# IoT_modules_atmega328_kinemata_v2.net
KiCad netlist of a schematic drawn in EAGLE
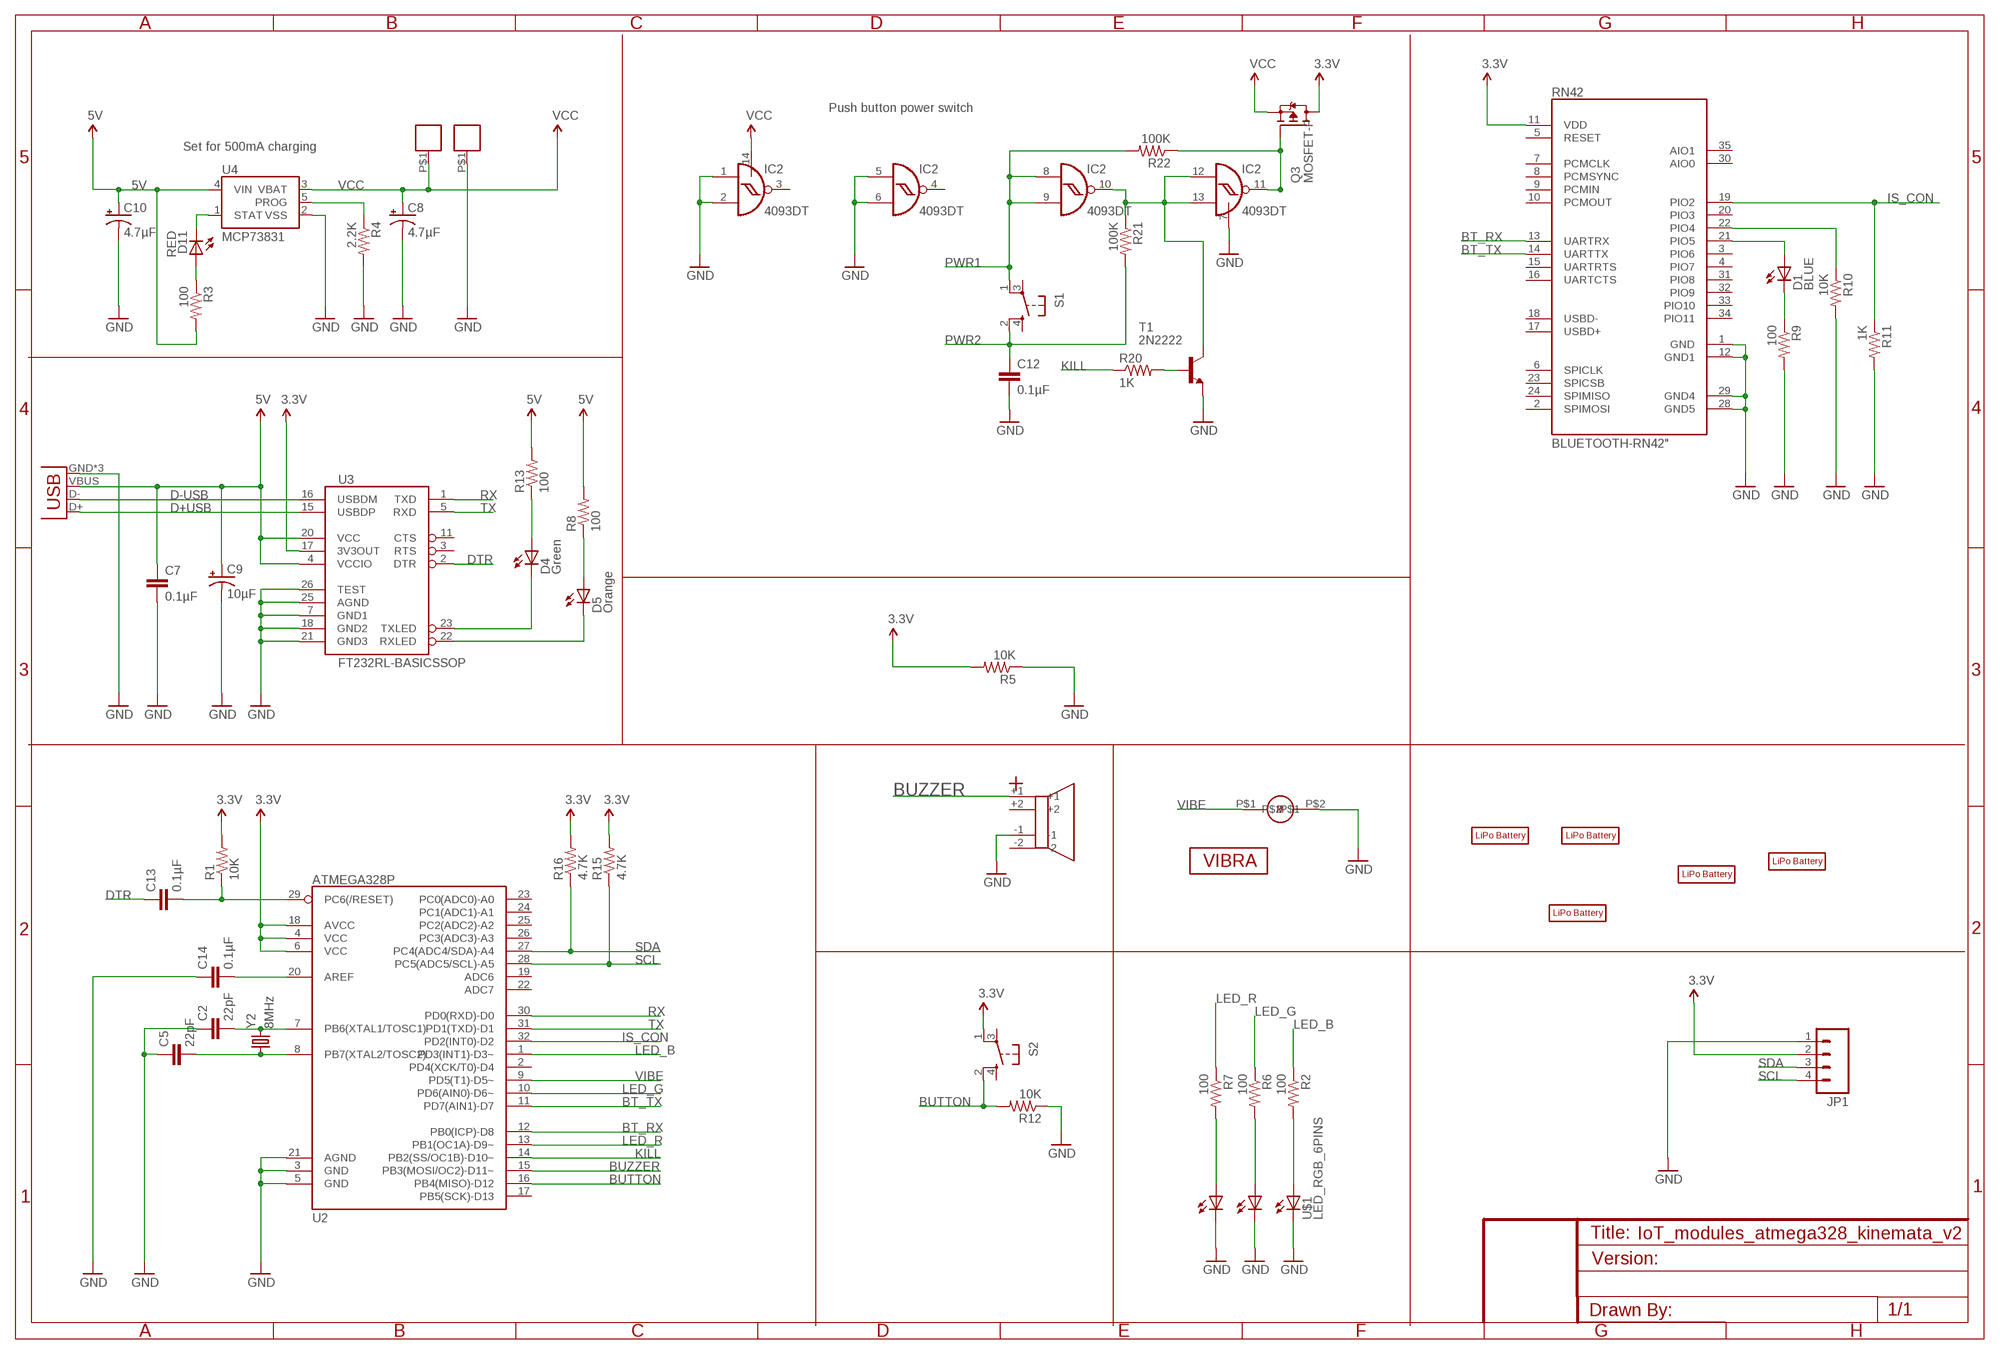
[diagram p0: schematic, sheet 1]

(export (version "E")
  (design (tool "Eeschema 10.0.6"))
  (components
    (comp (ref "BAT+2")
      (value "LIPO_PAD")
      (footprint "eagle-import:LIPO_PAD")
      (libsource (lib "eagle-import") (part "LIPO_PAD"))
    )
    (comp (ref "BAT-1")
      (value "LIPO_PAD")
      (footprint "eagle-import:LIPO_PAD")
      (libsource (lib "eagle-import") (part "LIPO_PAD"))
    )
    (comp (ref "C2")
      (value "22pF")
      (footprint "eagle-import:1206")
      (libsource (lib "eagle-import") (part "CAP1206"))
    )
    (comp (ref "C5")
      (value "22pF")
      (footprint "eagle-import:1206")
      (libsource (lib "eagle-import") (part "CAP1206"))
    )
    (comp (ref "C7")
      (value "0.1µF")
      (footprint "eagle-import:1206")
      (libsource (lib "eagle-import") (part "CAP1206"))
    )
    (comp (ref "C8")
      (value "4.7µF")
      (footprint "eagle-import:EIA3216")
      (libsource (lib "eagle-import") (part "CAP_POL1206"))
    )
    (comp (ref "C9")
      (value "10µF")
      (footprint "eagle-import:EIA3216")
      (libsource (lib "eagle-import") (part "CAP_POL1206"))
    )
    (comp (ref "C10")
      (value "4.7µF")
      (footprint "eagle-import:EIA3216")
      (libsource (lib "eagle-import") (part "CAP_POL1206"))
    )
    (comp (ref "C12")
      (value "0.1µF")
      (footprint "eagle-import:1206")
      (libsource (lib "eagle-import") (part "CAP1206"))
    )
    (comp (ref "C13")
      (value "0.1µF")
      (footprint "eagle-import:1206")
      (libsource (lib "eagle-import") (part "CAP1206"))
    )
    (comp (ref "C14")
      (value "0.1µF")
      (footprint "eagle-import:1206")
      (libsource (lib "eagle-import") (part "CAP1206"))
    )
    (comp (ref "D1")
      (value "BLUE")
      (footprint "eagle-import:LED-1206")
      (libsource (lib "eagle-import") (part "LED1206"))
    )
    (comp (ref "D4")
      (value "Green")
      (footprint "eagle-import:LED-1206")
      (libsource (lib "eagle-import") (part "LED1206"))
    )
    (comp (ref "D5")
      (value "Orange")
      (footprint "eagle-import:LED-1206")
      (libsource (lib "eagle-import") (part "LED1206"))
    )
    (comp (ref "D11")
      (value "RED")
      (footprint "eagle-import:LED-1206")
      (libsource (lib "eagle-import") (part "LED1206"))
    )
    (comp (ref "IC2")
      (value "4093DT")
      (footprint "eagle-import:MC14093B-TSSOP14")
      (libsource (lib "eagle-import") (part "4093DT"))
    )
    (comp (ref "JP1")
      (value "M04LONGPADS")
      (footprint "eagle-import:1X04_LONGPADS")
      (libsource (lib "eagle-import") (part "M04LONGPADS"))
    )
    (comp (ref "JP6")
      (value "USB-MICROB")
      (footprint "eagle-import:USB-MICROB")
      (libsource (lib "eagle-import") (part "USB-MICROB"))
    )
    (comp (ref "Q3")
      (value "MOSFET-P")
      (footprint "eagle-import:SOT23")
      (libsource (lib "eagle-import") (part "MOSFET-P"))
    )
    (comp (ref "R1")
      (value "10K")
      (footprint "eagle-import:1206")
      (libsource (lib "eagle-import") (part "RESISTOR1206"))
    )
    (comp (ref "R2")
      (value "100")
      (footprint "eagle-import:1206")
      (libsource (lib "eagle-import") (part "RESISTOR1206"))
    )
    (comp (ref "R3")
      (value "100")
      (footprint "eagle-import:1206")
      (libsource (lib "eagle-import") (part "RESISTOR1206"))
    )
    (comp (ref "R4")
      (value "2.2K")
      (footprint "eagle-import:1206")
      (libsource (lib "eagle-import") (part "RESISTOR1206"))
    )
    (comp (ref "R5")
      (value "10K")
      (footprint "eagle-import:1206")
      (libsource (lib "eagle-import") (part "RESISTOR1206"))
    )
    (comp (ref "R6")
      (value "100")
      (footprint "eagle-import:1206")
      (libsource (lib "eagle-import") (part "RESISTOR1206"))
    )
    (comp (ref "R7")
      (value "100")
      (footprint "eagle-import:1206")
      (libsource (lib "eagle-import") (part "RESISTOR1206"))
    )
    (comp (ref "R8")
      (value "100")
      (footprint "eagle-import:1206")
      (libsource (lib "eagle-import") (part "RESISTOR1206"))
    )
    (comp (ref "R9")
      (value "100")
      (footprint "eagle-import:1206")
      (libsource (lib "eagle-import") (part "RESISTOR1206"))
    )
    (comp (ref "R10")
      (value "10K")
      (footprint "eagle-import:1206")
      (libsource (lib "eagle-import") (part "RESISTOR1206"))
    )
    (comp (ref "R11")
      (value "1K")
      (footprint "eagle-import:1206")
      (libsource (lib "eagle-import") (part "RESISTOR1206"))
    )
    (comp (ref "R12")
      (value "10K")
      (footprint "eagle-import:1206")
      (libsource (lib "eagle-import") (part "RESISTOR1206"))
    )
    (comp (ref "R13")
      (value "100")
      (footprint "eagle-import:1206")
      (libsource (lib "eagle-import") (part "RESISTOR1206"))
    )
    (comp (ref "R15")
      (value "4.7K")
      (footprint "eagle-import:1206")
      (libsource (lib "eagle-import") (part "RESISTOR1206"))
    )
    (comp (ref "R16")
      (value "4.7K")
      (footprint "eagle-import:1206")
      (libsource (lib "eagle-import") (part "RESISTOR1206"))
    )
    (comp (ref "R20")
      (value "1K")
      (footprint "eagle-import:1206")
      (libsource (lib "eagle-import") (part "RESISTOR1206"))
    )
    (comp (ref "R21")
      (value "100K")
      (footprint "eagle-import:1206")
      (libsource (lib "eagle-import") (part "RESISTOR1206"))
    )
    (comp (ref "R22")
      (value "100K")
      (footprint "eagle-import:1206")
      (libsource (lib "eagle-import") (part "RESISTOR1206"))
    )
    (comp (ref "RN42")
      (value "BLUETOOTH-RN42\"")
      (footprint "eagle-import:RN42")
      (libsource (lib "eagle-import") (part "BLUETOOTH-RN42{dblquote}"))
    )
    (comp (ref "S1")
      (value "TAC_SWITCH_SIDEWAY")
      (footprint "eagle-import:TACTILE_SWITCH_ANGLE_SMD")
      (libsource (lib "eagle-import") (part "TAC_SWITCH_SIDEWAY"))
    )
    (comp (ref "S2")
      (value "TAC_SWITCH_SIDEWAY")
      (footprint "eagle-import:TACTILE_SWITCH_ANGLE_SMD")
      (libsource (lib "eagle-import") (part "TAC_SWITCH_SIDEWAY"))
    )
    (comp (ref "T1")
      (value "2N2222")
      (footprint "eagle-import:TO92-EBC-OVAL")
      (libsource (lib "eagle-import") (part "2N2222"))
    )
    (comp (ref "U$1")
      (value "LED_RGB_6PINS")
      (footprint "eagle-import:LED_RGB_6PINS")
      (libsource (lib "eagle-import") (part "LED_RGB_6PINS"))
    )
    (comp (ref "U$2")
      (value "LIPO_BATTERY110MAH")
      (footprint "eagle-import:LIPO_BATTERY_110MAH")
      (libsource (lib "eagle-import") (part "LIPO_BATTERY110MAH"))
    )
    (comp (ref "U$3")
      (value "BUZZER_4PINS")
      (footprint "eagle-import:FARNELL_BUZZER_MAGNETIC_SMD_3V_2215091")
      (libsource (lib "eagle-import") (part "BUZZER_4PINS"))
    )
    (comp (ref "U$4")
      (value "VIBRATION_MOTOR_SHAPE")
      (footprint "eagle-import:VIBRATION_MOTOR_SHAPE")
      (libsource (lib "eagle-import") (part "VIBRATION_MOTOR_SHAPE"))
    )
    (comp (ref "U$5")
      (value "VIBRATION_MOTOR")
      (footprint "eagle-import:VIBRATION_MOTOR_CABLE")
      (libsource (lib "eagle-import") (part "VIBRATION_MOTOR"))
    )
    (comp (ref "U$6")
      (value "LIPO_BATTERY300MAH")
      (footprint "eagle-import:LIPO_BATTERY_300MAH_FARNELL_2077884")
      (libsource (lib "eagle-import") (part "LIPO_BATTERY300MAH"))
    )
    (comp (ref "U$7")
      (value "LIPO_BATTERY400MAH")
      (footprint "eagle-import:LIPO_BATTERY_400MAH")
      (libsource (lib "eagle-import") (part "LIPO_BATTERY400MAH"))
    )
    (comp (ref "U$8")
      (value "LIPO_BATTERY600MAH")
      (footprint "eagle-import:LIPO_BATTERY_600MAH_FARNELL_2077883")
      (libsource (lib "eagle-import") (part "LIPO_BATTERY600MAH"))
    )
    (comp (ref "U$9")
      (value "LIPO_BATTERY900MAH")
      (footprint "eagle-import:LIPO_BATTERY_900MAH")
      (libsource (lib "eagle-import") (part "LIPO_BATTERY900MAH"))
    )
    (comp (ref "U2")
      (value "ATMEGA328P")
      (footprint "eagle-import:TQFP32-08")
      (libsource (lib "eagle-import") (part "ATMEGA328_SMT"))
    )
    (comp (ref "U3")
      (value "FT232RL-BASICSSOP")
      (footprint "eagle-import:SSOP28DB")
      (libsource (lib "eagle-import") (part "FT232RL-BASICSSOP"))
    )
    (comp (ref "U4")
      (value "MCP73831")
      (footprint "eagle-import:SOT23-5")
      (libsource (lib "eagle-import") (part "MCP73831"))
    )
    (comp (ref "Y2")
      (value "8MHz")
      (footprint "eagle-import:CRYSTAL_8MHZ_SMD_FARNELL_2101329")
      (libsource (lib "eagle-import") (part "CRYSTAL_2PINS5X3.2"))
    )
  )
  (nets
    (net (code "1") (name "/BT_RX") (class "Default")
      (node (ref "RN42") (pin "13") (pinfunction "UARTRX_13") (pintype "bidirectional"))
      (node (ref "U2") (pin "12") (pinfunction "PB0(ICP)-D8_12") (pintype "bidirectional"))
    )
    (net (code "2") (name "/BT_TX") (class "Default")
      (node (ref "RN42") (pin "14") (pinfunction "UARTTX_14") (pintype "bidirectional"))
      (node (ref "U2") (pin "11") (pinfunction "PD7(AIN1)-D7_11") (pintype "bidirectional"))
    )
    (net (code "3") (name "/BUTTON") (class "Default")
      (node (ref "R12") (pin "2") (pinfunction "2_2") (pintype "passive"))
      (node (ref "S2") (pin "2") (pinfunction "B2_2") (pintype "passive"))
      (node (ref "U2") (pin "16") (pinfunction "PB4(MISO)-D12_16") (pintype "bidirectional"))
    )
    (net (code "4") (name "/BUZZER") (class "Default")
      (node (ref "U$3") (pin "+1") (pinfunction "+1_+1") (pintype "bidirectional"))
      (node (ref "U2") (pin "15") (pinfunction "PB3(MOSI/OC2)-D11~{}_15") (pintype "bidirectional"))
    )
    (net (code "5") (name "/D+USB") (class "Default")
      (node (ref "JP6") (pin "D+") (pinfunction "D+_D+") (pintype "bidirectional"))
      (node (ref "U3") (pin "15") (pinfunction "USBDP_15") (pintype "bidirectional"))
    )
    (net (code "6") (name "/D-USB") (class "Default")
      (node (ref "JP6") (pin "D-") (pinfunction "D-_D-") (pintype "bidirectional"))
      (node (ref "U3") (pin "16") (pinfunction "USBDM_16") (pintype "bidirectional"))
    )
    (net (code "7") (name "/DTR") (class "Default")
      (node (ref "C13") (pin "1") (pinfunction "1_1") (pintype "passive"))
      (node (ref "U3") (pin "2") (pinfunction "DTR_2") (pintype "bidirectional"))
    )
    (net (code "8") (name "/IS_CON") (class "Default")
      (node (ref "R11") (pin "1") (pinfunction "1_1") (pintype "passive"))
      (node (ref "RN42") (pin "19") (pinfunction "PIO2_19") (pintype "bidirectional"))
      (node (ref "U2") (pin "32") (pinfunction "PD2(INT0)-D2_32") (pintype "bidirectional"))
    )
    (net (code "9") (name "/KILL") (class "Default")
      (node (ref "R20") (pin "1") (pinfunction "1_1") (pintype "passive"))
      (node (ref "U2") (pin "14") (pinfunction "PB2(SS/OC1B)-D10~{}_14") (pintype "bidirectional"))
    )
    (net (code "10") (name "/LED_B") (class "Default")
      (node (ref "R2") (pin "1") (pinfunction "1_1") (pintype "passive"))
      (node (ref "U2") (pin "1") (pinfunction "PD3(INT1)-D3~{}_1") (pintype "bidirectional"))
    )
    (net (code "11") (name "/LED_G") (class "Default")
      (node (ref "R6") (pin "1") (pinfunction "1_1") (pintype "passive"))
      (node (ref "U2") (pin "10") (pinfunction "PD6(AIN0)-D6~{}_10") (pintype "bidirectional"))
    )
    (net (code "12") (name "/LED_R") (class "Default")
      (node (ref "R7") (pin "1") (pinfunction "1_1") (pintype "passive"))
      (node (ref "U2") (pin "13") (pinfunction "PB1(OC1A)-D9~{}_13") (pintype "bidirectional"))
    )
    (net (code "13") (name "/PWR1") (class "Default")
      (node (ref "IC2") (pin "8") (pinfunction "8_8") (pintype "input"))
      (node (ref "IC2") (pin "9") (pinfunction "9_9") (pintype "input"))
      (node (ref "R22") (pin "2") (pinfunction "2_2") (pintype "passive"))
      (node (ref "S1") (pin "1") (pinfunction "A2_1") (pintype "passive"))
    )
    (net (code "14") (name "/PWR2") (class "Default")
      (node (ref "C12") (pin "1") (pinfunction "1_1") (pintype "passive"))
      (node (ref "R21") (pin "2") (pinfunction "2_2") (pintype "passive"))
      (node (ref "S1") (pin "2") (pinfunction "B2_2") (pintype "passive"))
    )
    (net (code "15") (name "/RX") (class "Default")
      (node (ref "U2") (pin "30") (pinfunction "PD0(RXD)-D0_30") (pintype "bidirectional"))
      (node (ref "U3") (pin "1") (pinfunction "TXD_1") (pintype "output"))
    )
    (net (code "16") (name "/SCL") (class "Default")
      (node (ref "JP1") (pin "4") (pinfunction "4_4") (pintype "passive"))
      (node (ref "R15") (pin "1") (pinfunction "1_1") (pintype "passive"))
      (node (ref "U2") (pin "28") (pinfunction "PC5(ADC5/SCL)-A5_28") (pintype "bidirectional"))
    )
    (net (code "17") (name "/SDA") (class "Default")
      (node (ref "JP1") (pin "3") (pinfunction "3_3") (pintype "passive"))
      (node (ref "R16") (pin "1") (pinfunction "1_1") (pintype "passive"))
      (node (ref "U2") (pin "27") (pinfunction "PC4(ADC4/SDA)-A4_27") (pintype "bidirectional"))
    )
    (net (code "18") (name "/TX") (class "Default")
      (node (ref "U2") (pin "31") (pinfunction "PD1(TXD)-D1_31") (pintype "bidirectional"))
      (node (ref "U3") (pin "5") (pinfunction "RXD_5") (pintype "input"))
    )
    (net (code "19") (name "/VIBE") (class "Default")
      (node (ref "U$5") (pin "P$1") (pinfunction "P$1_P$1") (pintype "bidirectional"))
      (node (ref "U2") (pin "9") (pinfunction "PD5(T1)-D5~{}_9") (pintype "bidirectional"))
    )
    (net (code "20") (name "3.3V") (class "Default")
      (node (ref "JP1") (pin "2") (pinfunction "2_2") (pintype "passive"))
      (node (ref "Q3") (pin "3") (pinfunction "D_3") (pintype "passive"))
      (node (ref "R1") (pin "2") (pinfunction "2_2") (pintype "passive"))
      (node (ref "R15") (pin "2") (pinfunction "2_2") (pintype "passive"))
      (node (ref "R16") (pin "2") (pinfunction "2_2") (pintype "passive"))
      (node (ref "R5") (pin "2") (pinfunction "2_2") (pintype "passive"))
      (node (ref "RN42") (pin "11") (pinfunction "VDD_11") (pintype "bidirectional"))
      (node (ref "S2") (pin "1") (pinfunction "A2_1") (pintype "passive"))
      (node (ref "U2") (pin "18") (pinfunction "AVCC_18") (pintype "bidirectional"))
      (node (ref "U2") (pin "4") (pinfunction "VCC_4") (pintype "bidirectional"))
      (node (ref "U2") (pin "6") (pinfunction "VCC_6") (pintype "bidirectional"))
      (node (ref "U3") (pin "17") (pinfunction "3V3OUT_17") (pintype "output"))
    )
    (net (code "21") (name "5V") (class "Default")
      (node (ref "C10") (pin "A") (pinfunction "+_A") (pintype "passive"))
      (node (ref "C7") (pin "1") (pinfunction "1_1") (pintype "passive"))
      (node (ref "C9") (pin "A") (pinfunction "+_A") (pintype "passive"))
      (node (ref "JP6") (pin "VBUS") (pinfunction "VBUS_VBUS") (pintype "bidirectional"))
      (node (ref "R13") (pin "2") (pinfunction "2_2") (pintype "passive"))
      (node (ref "R3") (pin "2") (pinfunction "2_2") (pintype "passive"))
      (node (ref "R8") (pin "2") (pinfunction "2_2") (pintype "passive"))
      (node (ref "U3") (pin "20") (pinfunction "VCC_20") (pintype "power_in"))
      (node (ref "U3") (pin "4") (pinfunction "VCCIO_4") (pintype "power_in"))
      (node (ref "U4") (pin "4") (pinfunction "VIN_4") (pintype "power_in"))
    )
    (net (code "22") (name "GND") (class "Default")
      (node (ref "BAT-1") (pin "P$1") (pinfunction "P$1_P$1") (pintype "power_in"))
      (node (ref "C10") (pin "C") (pinfunction "-_C") (pintype "passive"))
      (node (ref "C12") (pin "2") (pinfunction "2_2") (pintype "passive"))
      (node (ref "C14") (pin "1") (pinfunction "1_1") (pintype "passive"))
      (node (ref "C2") (pin "1") (pinfunction "1_1") (pintype "passive"))
      (node (ref "C5") (pin "1") (pinfunction "1_1") (pintype "passive"))
      (node (ref "C7") (pin "2") (pinfunction "2_2") (pintype "passive"))
      (node (ref "C8") (pin "C") (pinfunction "-_C") (pintype "passive"))
      (node (ref "C9") (pin "C") (pinfunction "-_C") (pintype "passive"))
      (node (ref "IC2") (pin "1") (pinfunction "1_1") (pintype "input"))
      (node (ref "IC2") (pin "2") (pinfunction "2_2") (pintype "input"))
      (node (ref "IC2") (pin "5") (pinfunction "5_5") (pintype "input"))
      (node (ref "IC2") (pin "6") (pinfunction "6_6") (pintype "input"))
      (node (ref "IC2") (pin "7") (pinfunction "7_7") (pintype "power_in"))
      (node (ref "JP1") (pin "1") (pinfunction "1_1") (pintype "passive"))
      (node (ref "JP6") (pin "GND") (pinfunction "GND_GND") (pintype "bidirectional"))
      (node (ref "JP6") (pin "MT1") (pinfunction "GND_MT1") (pintype "bidirectional"))
      (node (ref "JP6") (pin "MT2") (pinfunction "GND_MT2") (pintype "bidirectional"))
      (node (ref "R10") (pin "2") (pinfunction "2_2") (pintype "passive"))
      (node (ref "R11") (pin "2") (pinfunction "2_2") (pintype "passive"))
      (node (ref "R12") (pin "1") (pinfunction "1_1") (pintype "passive"))
      (node (ref "R4") (pin "2") (pinfunction "2_2") (pintype "passive"))
      (node (ref "R5") (pin "1") (pinfunction "1_1") (pintype "passive"))
      (node (ref "R9") (pin "2") (pinfunction "2_2") (pintype "passive"))
      (node (ref "RN42") (pin "1") (pinfunction "GND_1") (pintype "bidirectional"))
      (node (ref "RN42") (pin "12") (pinfunction "GND1_12") (pintype "bidirectional"))
      (node (ref "RN42") (pin "28") (pinfunction "GND5_28") (pintype "bidirectional"))
      (node (ref "RN42") (pin "29") (pinfunction "GND4_29") (pintype "bidirectional"))
      (node (ref "T1") (pin "E") (pinfunction "E_E") (pintype "passive"))
      (node (ref "U$1") (pin "BC") (pinfunction "BC_BC") (pintype "passive"))
      (node (ref "U$1") (pin "GC") (pinfunction "GC_GC") (pintype "passive"))
      (node (ref "U$1") (pin "RC") (pinfunction "RC_RC") (pintype "passive"))
      (node (ref "U$3") (pin "-1") (pinfunction "-1_-1") (pintype "bidirectional"))
      (node (ref "U$5") (pin "P$2") (pinfunction "P$2_P$2") (pintype "bidirectional"))
      (node (ref "U2") (pin "21") (pinfunction "AGND_21") (pintype "bidirectional"))
      (node (ref "U2") (pin "3") (pinfunction "GND_3") (pintype "bidirectional"))
      (node (ref "U2") (pin "5") (pinfunction "GND_5") (pintype "bidirectional"))
      (node (ref "U3") (pin "18") (pinfunction "GND2_18") (pintype "power_in"))
      (node (ref "U3") (pin "21") (pinfunction "GND3_21") (pintype "power_in"))
      (node (ref "U3") (pin "25") (pinfunction "AGND_25") (pintype "power_in"))
      (node (ref "U3") (pin "26") (pinfunction "TEST_26") (pintype "input"))
      (node (ref "U3") (pin "7") (pinfunction "GND1_7") (pintype "power_in"))
      (node (ref "U4") (pin "2") (pinfunction "VSS_2") (pintype "power_in"))
    )
    (net (code "23") (name "Net-(D1-PadC)") (class "Default")
      (node (ref "D1") (pin "C") (pinfunction "C_C") (pintype "passive"))
      (node (ref "R9") (pin "1") (pinfunction "1_1") (pintype "passive"))
    )
    (net (code "24") (name "Net-(D4-PadA)") (class "Default")
      (node (ref "D4") (pin "A") (pinfunction "A_A") (pintype "passive"))
      (node (ref "R13") (pin "1") (pinfunction "1_1") (pintype "passive"))
    )
    (net (code "25") (name "Net-(D5-PadA)") (class "Default")
      (node (ref "D5") (pin "A") (pinfunction "A_A") (pintype "passive"))
      (node (ref "R8") (pin "1") (pinfunction "1_1") (pintype "passive"))
    )
    (net (code "26") (name "Net-(D11-PadA)") (class "Default")
      (node (ref "D11") (pin "A") (pinfunction "A_A") (pintype "passive"))
      (node (ref "R3") (pin "1") (pinfunction "1_1") (pintype "passive"))
    )
    (net (code "27") (name "Net-(IC2-Pad10)") (class "Default")
      (node (ref "IC2") (pin "10") (pinfunction "10_10") (pintype "output"))
      (node (ref "IC2") (pin "12") (pinfunction "12_12") (pintype "input"))
      (node (ref "IC2") (pin "13") (pinfunction "13_13") (pintype "input"))
      (node (ref "R21") (pin "1") (pinfunction "1_1") (pintype "passive"))
      (node (ref "T1") (pin "C") (pinfunction "C_C") (pintype "passive"))
    )
    (net (code "28") (name "Net-(Q3-G)") (class "Default")
      (node (ref "IC2") (pin "11") (pinfunction "11_11") (pintype "output"))
      (node (ref "Q3") (pin "1") (pinfunction "G_1") (pintype "passive"))
      (node (ref "R22") (pin "1") (pinfunction "1_1") (pintype "passive"))
    )
    (net (code "29") (name "Net-(R2-Pad2)") (class "Default")
      (node (ref "R2") (pin "2") (pinfunction "2_2") (pintype "passive"))
      (node (ref "U$1") (pin "GA") (pinfunction "GA_GA") (pintype "passive"))
    )
    (net (code "30") (name "Net-(R6-Pad2)") (class "Default")
      (node (ref "R6") (pin "2") (pinfunction "2_2") (pintype "passive"))
      (node (ref "U$1") (pin "RA") (pinfunction "RA_RA") (pintype "passive"))
    )
    (net (code "31") (name "Net-(R7-Pad2)") (class "Default")
      (node (ref "R7") (pin "2") (pinfunction "2_2") (pintype "passive"))
      (node (ref "U$1") (pin "BA") (pinfunction "BA_BA") (pintype "passive"))
    )
    (net (code "32") (name "Net-(R20-Pad2)") (class "Default")
      (node (ref "R20") (pin "2") (pinfunction "2_2") (pintype "passive"))
      (node (ref "T1") (pin "B") (pinfunction "B_B") (pintype "passive"))
    )
    (net (code "33") (name "Net-(RN42-PIO4)") (class "Default")
      (node (ref "R10") (pin "1") (pinfunction "1_1") (pintype "passive"))
      (node (ref "RN42") (pin "22") (pinfunction "PIO4_22") (pintype "bidirectional"))
    )
    (net (code "34") (name "Net-(RN42-PIO5)") (class "Default")
      (node (ref "D1") (pin "A") (pinfunction "A_A") (pintype "passive"))
      (node (ref "RN42") (pin "21") (pinfunction "PIO5_21") (pintype "bidirectional"))
    )
    (net (code "35") (name "Net-(U2-AREF)") (class "Default")
      (node (ref "C14") (pin "2") (pinfunction "2_2") (pintype "passive"))
      (node (ref "U2") (pin "20") (pinfunction "AREF_20") (pintype "bidirectional"))
    )
    (net (code "36") (name "Net-(U2-PB6(XTAL1{slash}TOSC1))") (class "Default")
      (node (ref "C2") (pin "2") (pinfunction "2_2") (pintype "passive"))
      (node (ref "U2") (pin "7") (pinfunction "PB6(XTAL1/TOSC1)_7") (pintype "bidirectional"))
      (node (ref "Y2") (pin "P$2") (pinfunction "2_P$2") (pintype "passive"))
    )
    (net (code "37") (name "Net-(U2-PB7(XTAL2{slash}TOSC2))") (class "Default")
      (node (ref "C5") (pin "2") (pinfunction "2_2") (pintype "passive"))
      (node (ref "U2") (pin "8") (pinfunction "PB7(XTAL2/TOSC2)_8") (pintype "bidirectional"))
      (node (ref "Y2") (pin "P$1") (pinfunction "1_P$1") (pintype "passive"))
    )
    (net (code "38") (name "Net-(U2-PC6({slash}RESET))") (class "Default")
      (node (ref "C13") (pin "2") (pinfunction "2_2") (pintype "passive"))
      (node (ref "R1") (pin "1") (pinfunction "1_1") (pintype "passive"))
      (node (ref "U2") (pin "29") (pinfunction "PC6(/RESET)_29") (pintype "bidirectional"))
    )
    (net (code "39") (name "Net-(U3-RXLED)") (class "Default")
      (node (ref "D5") (pin "C") (pinfunction "C_C") (pintype "passive"))
      (node (ref "U3") (pin "22") (pinfunction "RXLED_22") (pintype "bidirectional"))
    )
    (net (code "40") (name "Net-(U3-TXLED)") (class "Default")
      (node (ref "D4") (pin "C") (pinfunction "C_C") (pintype "passive"))
      (node (ref "U3") (pin "23") (pinfunction "TXLED_23") (pintype "bidirectional"))
    )
    (net (code "41") (name "Net-(U4-PROG)") (class "Default")
      (node (ref "R4") (pin "1") (pinfunction "1_1") (pintype "passive"))
      (node (ref "U4") (pin "5") (pinfunction "PROG_5") (pintype "input"))
    )
    (net (code "42") (name "Net-(U4-STAT)") (class "Default")
      (node (ref "D11") (pin "C") (pinfunction "C_C") (pintype "passive"))
      (node (ref "U4") (pin "1") (pinfunction "STAT_1") (pintype "output"))
    )
    (net (code "43") (name "VCC") (class "Default")
      (node (ref "BAT+2") (pin "P$1") (pinfunction "P$1_P$1") (pintype "power_in"))
      (node (ref "C8") (pin "A") (pinfunction "+_A") (pintype "passive"))
      (node (ref "IC2") (pin "14") (pinfunction "14_14") (pintype "power_in"))
      (node (ref "Q3") (pin "2") (pinfunction "S_2") (pintype "passive"))
      (node (ref "U4") (pin "3") (pinfunction "VBAT_3") (pintype "power_in"))
    )
    (net (code "44") (name "unconnected-(IC2-Pad3)") (class "Default")
      (node (ref "IC2") (pin "3") (pinfunction "3_3") (pintype "output"))
    )
    (net (code "45") (name "unconnected-(IC2-Pad4)") (class "Default")
      (node (ref "IC2") (pin "4") (pinfunction "4_4") (pintype "output"))
    )
    (net (code "46") (name "unconnected-(RN42-AIO0-Pad30)") (class "Default")
      (node (ref "RN42") (pin "30") (pinfunction "AIO0_30") (pintype "bidirectional"))
    )
    (net (code "47") (name "unconnected-(RN42-AIO1-Pad35)") (class "Default")
      (node (ref "RN42") (pin "35") (pinfunction "AIO1_35") (pintype "bidirectional"))
    )
    (net (code "48") (name "unconnected-(RN42-PCMCLK-Pad7)") (class "Default")
      (node (ref "RN42") (pin "7") (pinfunction "PCMCLK_7") (pintype "bidirectional"))
    )
    (net (code "49") (name "unconnected-(RN42-PCMIN-Pad9)") (class "Default")
      (node (ref "RN42") (pin "9") (pinfunction "PCMIN_9") (pintype "bidirectional"))
    )
    (net (code "50") (name "unconnected-(RN42-PCMOUT-Pad10)") (class "Default")
      (node (ref "RN42") (pin "10") (pinfunction "PCMOUT_10") (pintype "bidirectional"))
    )
    (net (code "51") (name "unconnected-(RN42-PCMSYNC-Pad8)") (class "Default")
      (node (ref "RN42") (pin "8") (pinfunction "PCMSYNC_8") (pintype "bidirectional"))
    )
    (net (code "52") (name "unconnected-(RN42-PIO3-Pad20)") (class "Default")
      (node (ref "RN42") (pin "20") (pinfunction "PIO3_20") (pintype "bidirectional"))
    )
    (net (code "53") (name "unconnected-(RN42-PIO6-Pad3)") (class "Default")
      (node (ref "RN42") (pin "3") (pinfunction "PIO6_3") (pintype "bidirectional"))
    )
    (net (code "54") (name "unconnected-(RN42-PIO7-Pad4)") (class "Default")
      (node (ref "RN42") (pin "4") (pinfunction "PIO7_4") (pintype "bidirectional"))
    )
    (net (code "55") (name "unconnected-(RN42-PIO8-Pad31)") (class "Default")
      (node (ref "RN42") (pin "31") (pinfunction "PIO8_31") (pintype "bidirectional"))
    )
    (net (code "56") (name "unconnected-(RN42-PIO9-Pad32)") (class "Default")
      (node (ref "RN42") (pin "32") (pinfunction "PIO9_32") (pintype "bidirectional"))
    )
    (net (code "57") (name "unconnected-(RN42-PIO10-Pad33)") (class "Default")
      (node (ref "RN42") (pin "33") (pinfunction "PIO10_33") (pintype "bidirectional"))
    )
    (net (code "58") (name "unconnected-(RN42-PIO11-Pad34)") (class "Default")
      (node (ref "RN42") (pin "34") (pinfunction "PIO11_34") (pintype "bidirectional"))
    )
    (net (code "59") (name "unconnected-(RN42-RESET-Pad5)") (class "Default")
      (node (ref "RN42") (pin "5") (pinfunction "RESET_5") (pintype "bidirectional"))
    )
    (net (code "60") (name "unconnected-(RN42-SPICLK-Pad6)") (class "Default")
      (node (ref "RN42") (pin "6") (pinfunction "SPICLK_6") (pintype "bidirectional"))
    )
    (net (code "61") (name "unconnected-(RN42-SPICSB-Pad23)") (class "Default")
      (node (ref "RN42") (pin "23") (pinfunction "SPICSB_23") (pintype "bidirectional"))
    )
    (net (code "62") (name "unconnected-(RN42-SPIMISO-Pad24)") (class "Default")
      (node (ref "RN42") (pin "24") (pinfunction "SPIMISO_24") (pintype "bidirectional"))
    )
    (net (code "63") (name "unconnected-(RN42-SPIMOSI-Pad2)") (class "Default")
      (node (ref "RN42") (pin "2") (pinfunction "SPIMOSI_2") (pintype "bidirectional"))
    )
    (net (code "64") (name "unconnected-(RN42-UARTCTS-Pad16)") (class "Default")
      (node (ref "RN42") (pin "16") (pinfunction "UARTCTS_16") (pintype "bidirectional"))
    )
    (net (code "65") (name "unconnected-(RN42-UARTRTS-Pad15)") (class "Default")
      (node (ref "RN42") (pin "15") (pinfunction "UARTRTS_15") (pintype "bidirectional"))
    )
    (net (code "66") (name "unconnected-(RN42-USBD+-Pad17)") (class "Default")
      (node (ref "RN42") (pin "17") (pinfunction "USBD+_17") (pintype "bidirectional"))
    )
    (net (code "67") (name "unconnected-(RN42-USBD--Pad18)") (class "Default")
      (node (ref "RN42") (pin "18") (pinfunction "USBD-_18") (pintype "bidirectional"))
    )
    (net (code "68") (name "unconnected-(S1-A1-Pad3)") (class "Default")
      (node (ref "S1") (pin "3") (pinfunction "A1_3") (pintype "passive"))
    )
    (net (code "69") (name "unconnected-(S1-B1-Pad4)") (class "Default")
      (node (ref "S1") (pin "4") (pinfunction "B1_4") (pintype "passive"))
    )
    (net (code "70") (name "unconnected-(S2-A1-Pad3)") (class "Default")
      (node (ref "S2") (pin "3") (pinfunction "A1_3") (pintype "passive"))
    )
    (net (code "71") (name "unconnected-(S2-B1-Pad4)") (class "Default")
      (node (ref "S2") (pin "4") (pinfunction "B1_4") (pintype "passive"))
    )
    (net (code "72") (name "unconnected-(U$3-Pad+2)") (class "Default")
      (node (ref "U$3") (pin "+2") (pinfunction "+2_+2") (pintype "bidirectional"))
    )
    (net (code "73") (name "unconnected-(U$3-Pad-2)") (class "Default")
      (node (ref "U$3") (pin "-2") (pinfunction "-2_-2") (pintype "bidirectional"))
    )
    (net (code "74") (name "unconnected-(U2-ADC6-Pad19)") (class "Default")
      (node (ref "U2") (pin "19") (pinfunction "ADC6_19") (pintype "bidirectional"))
    )
    (net (code "75") (name "unconnected-(U2-ADC7-Pad22)") (class "Default")
      (node (ref "U2") (pin "22") (pinfunction "ADC7_22") (pintype "bidirectional"))
    )
    (net (code "76") (name "unconnected-(U2-PB5(SCK)-D13-Pad17)") (class "Default")
      (node (ref "U2") (pin "17") (pinfunction "PB5(SCK)-D13_17") (pintype "bidirectional"))
    )
    (net (code "77") (name "unconnected-(U2-PC0(ADC0)-A0-Pad23)") (class "Default")
      (node (ref "U2") (pin "23") (pinfunction "PC0(ADC0)-A0_23") (pintype "bidirectional"))
    )
    (net (code "78") (name "unconnected-(U2-PC1(ADC1)-A1-Pad24)") (class "Default")
      (node (ref "U2") (pin "24") (pinfunction "PC1(ADC1)-A1_24") (pintype "bidirectional"))
    )
    (net (code "79") (name "unconnected-(U2-PC2(ADC2)-A2-Pad25)") (class "Default")
      (node (ref "U2") (pin "25") (pinfunction "PC2(ADC2)-A2_25") (pintype "bidirectional"))
    )
    (net (code "80") (name "unconnected-(U2-PC3(ADC3)-A3-Pad26)") (class "Default")
      (node (ref "U2") (pin "26") (pinfunction "PC3(ADC3)-A3_26") (pintype "bidirectional"))
    )
    (net (code "81") (name "unconnected-(U2-PD4(XCK{slash}T0)-D4-Pad2)") (class "Default")
      (node (ref "U2") (pin "2") (pinfunction "PD4(XCK/T0)-D4_2") (pintype "bidirectional"))
    )
    (net (code "82") (name "unconnected-(U3-CTS-Pad11)") (class "Default")
      (node (ref "U3") (pin "11") (pinfunction "CTS_11") (pintype "bidirectional"))
    )
    (net (code "83") (name "unconnected-(U3-RTS-Pad3)") (class "Default")
      (node (ref "U3") (pin "3") (pinfunction "RTS_3") (pintype "bidirectional"))
    )
  )
)
